# Horizontally_Mounted_Lighthouse.net
KiCad netlist of a schematic drawn in EAGLE
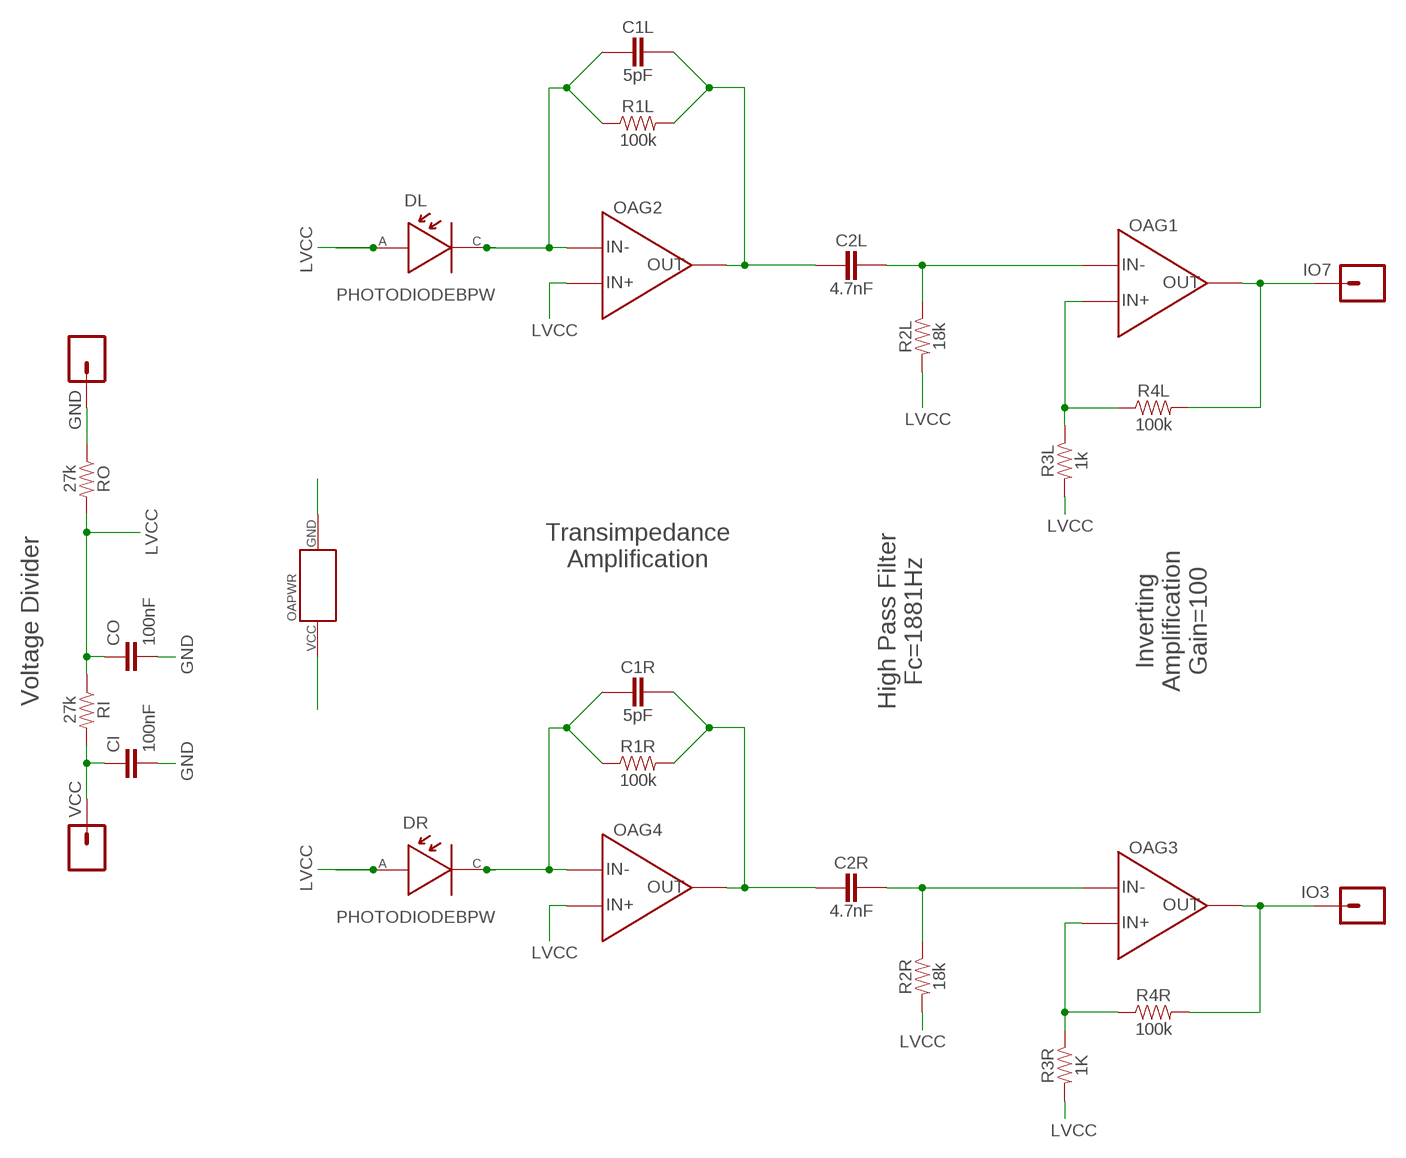
[diagram p0: schematic, sheet 1]

(export (version "E")
  (design (tool "Eeschema 10.0.6"))
  (components
    (comp (ref "C1L")
      (value "5pF")
      (footprint "eagle-import:PASSIVE-0603")
      (libsource (lib "eagle-import") (part "CAPACITOR"))
    )
    (comp (ref "C1R")
      (value "5pF")
      (footprint "eagle-import:PASSIVE-0603")
      (libsource (lib "eagle-import") (part "CAPACITOR"))
    )
    (comp (ref "C2L")
      (value "4.7nF")
      (footprint "eagle-import:PASSIVE-0603")
      (libsource (lib "eagle-import") (part "CAPACITOR"))
    )
    (comp (ref "C2R")
      (value "4.7nF")
      (footprint "eagle-import:PASSIVE-0603")
      (libsource (lib "eagle-import") (part "CAPACITOR"))
    )
    (comp (ref "CI")
      (value "100nF")
      (footprint "eagle-import:0603")
      (libsource (lib "eagle-import") (part "4.7PF-0603-50V-5%"))
    )
    (comp (ref "CO")
      (value "100nF")
      (footprint "eagle-import:0603")
      (libsource (lib "eagle-import") (part "4.7PF-0603-50V-5%"))
    )
    (comp (ref "DL")
      (value "PHOTODIODEBPW")
      (footprint "eagle-import:BPW34_BP104_SMD")
      (libsource (lib "eagle-import") (part "PHOTODIODEBPW"))
    )
    (comp (ref "DR")
      (value "PHOTODIODEBPW")
      (footprint "eagle-import:BPW34_BP104_SMD")
      (libsource (lib "eagle-import") (part "PHOTODIODEBPW"))
    )
    (comp (ref "GND")
      (value "CONN_01PTH_NO_SILK_YES_STOP")
      (footprint "eagle-import:1X01_NO_SILK")
      (libsource (lib "eagle-import") (part "CONN_01PTH_NO_SILK_YES_STOP"))
    )
    (comp (ref "IO3")
      (value "CONN_01PTH_NO_SILK_YES_STOP")
      (footprint "eagle-import:1X01_NO_SILK")
      (libsource (lib "eagle-import") (part "CONN_01PTH_NO_SILK_YES_STOP"))
    )
    (comp (ref "IO7")
      (value "CONN_01PTH_NO_SILK_YES_STOP")
      (footprint "eagle-import:1X01_NO_SILK")
      (libsource (lib "eagle-import") (part "CONN_01PTH_NO_SILK_YES_STOP"))
    )
    (comp (ref "OA")
      (value "TLV2464IPW")
      (footprint "eagle-import:PW14")
      (libsource (lib "eagle-import") (part "TLV2464IPW"))
    )
    (comp (ref "R1L")
      (value "100k")
      (footprint "eagle-import:PASSIVE-0603")
      (libsource (lib "eagle-import") (part "RESISTOR"))
    )
    (comp (ref "R1R")
      (value "100k")
      (footprint "eagle-import:PASSIVE-0603")
      (libsource (lib "eagle-import") (part "RESISTOR"))
    )
    (comp (ref "R2L")
      (value "18k")
      (footprint "eagle-import:PASSIVE-0603")
      (libsource (lib "eagle-import") (part "RESISTOR"))
    )
    (comp (ref "R2R")
      (value "18k")
      (footprint "eagle-import:PASSIVE-0603")
      (libsource (lib "eagle-import") (part "RESISTOR"))
    )
    (comp (ref "R3L")
      (value "1k")
      (footprint "eagle-import:PASSIVE-0603")
      (libsource (lib "eagle-import") (part "RESISTOR"))
    )
    (comp (ref "R3R")
      (value "1K")
      (footprint "eagle-import:PASSIVE-0603")
      (libsource (lib "eagle-import") (part "RESISTOR"))
    )
    (comp (ref "R4L")
      (value "100k")
      (footprint "eagle-import:PASSIVE-0603")
      (libsource (lib "eagle-import") (part "RESISTOR"))
    )
    (comp (ref "R4R")
      (value "100k")
      (footprint "eagle-import:PASSIVE-0603")
      (libsource (lib "eagle-import") (part "RESISTOR"))
    )
    (comp (ref "RI")
      (value "27k")
      (footprint "eagle-import:0603")
      (libsource (lib "eagle-import") (part "100KOHM-0603-1/10W-1%"))
    )
    (comp (ref "RO")
      (value "27k")
      (footprint "eagle-import:0603")
      (libsource (lib "eagle-import") (part "100KOHM-0603-1/10W-1%"))
    )
    (comp (ref "VCC")
      (value "CONN_01PTH_NO_SILK_YES_STOP")
      (footprint "eagle-import:1X01_NO_SILK")
      (libsource (lib "eagle-import") (part "CONN_01PTH_NO_SILK_YES_STOP"))
    )
  )
  (nets
    (net (code "1") (name "/GND") (class "Default")
      (node (ref "CI") (pin "2") (pinfunction "2_2") (pintype "passive"))
      (node (ref "CO") (pin "2") (pinfunction "2_2") (pintype "passive"))
      (node (ref "GND") (pin "1") (pinfunction "1_1") (pintype "passive"))
      (node (ref "OA") (pin "11") (pinfunction "GND_11") (pintype "bidirectional"))
      (node (ref "RO") (pin "1") (pinfunction "1_1") (pintype "passive"))
    )
    (net (code "2") (name "/IO3") (class "Default")
      (node (ref "IO3") (pin "1") (pinfunction "1_1") (pintype "passive"))
      (node (ref "OA") (pin "8") (pinfunction "OUT_8") (pintype "bidirectional"))
      (node (ref "R4R") (pin "2") (pinfunction "2_2") (pintype "passive"))
    )
    (net (code "3") (name "/IO7") (class "Default")
      (node (ref "IO7") (pin "1") (pinfunction "1_1") (pintype "passive"))
      (node (ref "OA") (pin "1") (pinfunction "OUT_1") (pintype "bidirectional"))
      (node (ref "R4L") (pin "2") (pinfunction "2_2") (pintype "passive"))
    )
    (net (code "4") (name "/LVCC") (class "Default")
      (node (ref "CO") (pin "1") (pinfunction "1_1") (pintype "passive"))
      (node (ref "DL") (pin "ANODE") (pinfunction "ANODE_ANODE") (pintype "bidirectional"))
      (node (ref "DR") (pin "ANODE") (pinfunction "ANODE_ANODE") (pintype "bidirectional"))
      (node (ref "OA") (pin "12") (pinfunction "IN+_12") (pintype "bidirectional"))
      (node (ref "OA") (pin "5") (pinfunction "IN+_5") (pintype "bidirectional"))
      (node (ref "R2L") (pin "2") (pinfunction "2_2") (pintype "passive"))
      (node (ref "R2R") (pin "2") (pinfunction "2_2") (pintype "passive"))
      (node (ref "R3L") (pin "2") (pinfunction "2_2") (pintype "passive"))
      (node (ref "R3R") (pin "2") (pinfunction "2_2") (pintype "passive"))
      (node (ref "RI") (pin "1") (pinfunction "1_1") (pintype "passive"))
      (node (ref "RO") (pin "2") (pinfunction "2_2") (pintype "passive"))
    )
    (net (code "5") (name "/VCC") (class "Default")
      (node (ref "CI") (pin "1") (pinfunction "1_1") (pintype "passive"))
      (node (ref "OA") (pin "4") (pinfunction "VCC_4") (pintype "bidirectional"))
      (node (ref "RI") (pin "2") (pinfunction "2_2") (pintype "passive"))
      (node (ref "VCC") (pin "1") (pinfunction "1_1") (pintype "passive"))
    )
    (net (code "6") (name "Net-(OAA-IN+)") (class "Default")
      (node (ref "OA") (pin "3") (pinfunction "IN+_3") (pintype "bidirectional"))
      (node (ref "R3L") (pin "1") (pinfunction "1_1") (pintype "passive"))
      (node (ref "R4L") (pin "1") (pinfunction "1_1") (pintype "passive"))
    )
    (net (code "7") (name "Net-(OAA-IN-)") (class "Default")
      (node (ref "C2L") (pin "2") (pinfunction "2_2") (pintype "passive"))
      (node (ref "OA") (pin "2") (pinfunction "IN-_2") (pintype "bidirectional"))
      (node (ref "R2L") (pin "1") (pinfunction "1_1") (pintype "passive"))
    )
    (net (code "8") (name "Net-(OAB-IN-)") (class "Default")
      (node (ref "C1L") (pin "1") (pinfunction "1_1") (pintype "passive"))
      (node (ref "DL") (pin "CATHODE") (pinfunction "CATHODE_CATHODE") (pintype "bidirectional"))
      (node (ref "OA") (pin "6") (pinfunction "IN-_6") (pintype "bidirectional"))
      (node (ref "R1L") (pin "1") (pinfunction "1_1") (pintype "passive"))
    )
    (net (code "9") (name "Net-(OAB-OUT)") (class "Default")
      (node (ref "C1L") (pin "2") (pinfunction "2_2") (pintype "passive"))
      (node (ref "C2L") (pin "1") (pinfunction "1_1") (pintype "passive"))
      (node (ref "OA") (pin "7") (pinfunction "OUT_7") (pintype "bidirectional"))
      (node (ref "R1L") (pin "2") (pinfunction "2_2") (pintype "passive"))
    )
    (net (code "10") (name "Net-(OAC-IN+)") (class "Default")
      (node (ref "OA") (pin "10") (pinfunction "IN+_10") (pintype "bidirectional"))
      (node (ref "R3R") (pin "1") (pinfunction "1_1") (pintype "passive"))
      (node (ref "R4R") (pin "1") (pinfunction "1_1") (pintype "passive"))
    )
    (net (code "11") (name "Net-(OAC-IN-)") (class "Default")
      (node (ref "C2R") (pin "2") (pinfunction "2_2") (pintype "passive"))
      (node (ref "OA") (pin "9") (pinfunction "IN-_9") (pintype "bidirectional"))
      (node (ref "R2R") (pin "1") (pinfunction "1_1") (pintype "passive"))
    )
    (net (code "12") (name "Net-(OAD-IN-)") (class "Default")
      (node (ref "C1R") (pin "1") (pinfunction "1_1") (pintype "passive"))
      (node (ref "DR") (pin "CATHODE") (pinfunction "CATHODE_CATHODE") (pintype "bidirectional"))
      (node (ref "OA") (pin "13") (pinfunction "IN-_13") (pintype "bidirectional"))
      (node (ref "R1R") (pin "1") (pinfunction "1_1") (pintype "passive"))
    )
    (net (code "13") (name "Net-(OAD-OUT)") (class "Default")
      (node (ref "C1R") (pin "2") (pinfunction "2_2") (pintype "passive"))
      (node (ref "C2R") (pin "1") (pinfunction "1_1") (pintype "passive"))
      (node (ref "OA") (pin "14") (pinfunction "OUT_14") (pintype "bidirectional"))
      (node (ref "R1R") (pin "2") (pinfunction "2_2") (pintype "passive"))
    )
  )
)
